# Pg8_JTAG_Interface_LEDs_Decoupling_Capac.net
KiCad netlist of a schematic drawn in Altium Designer
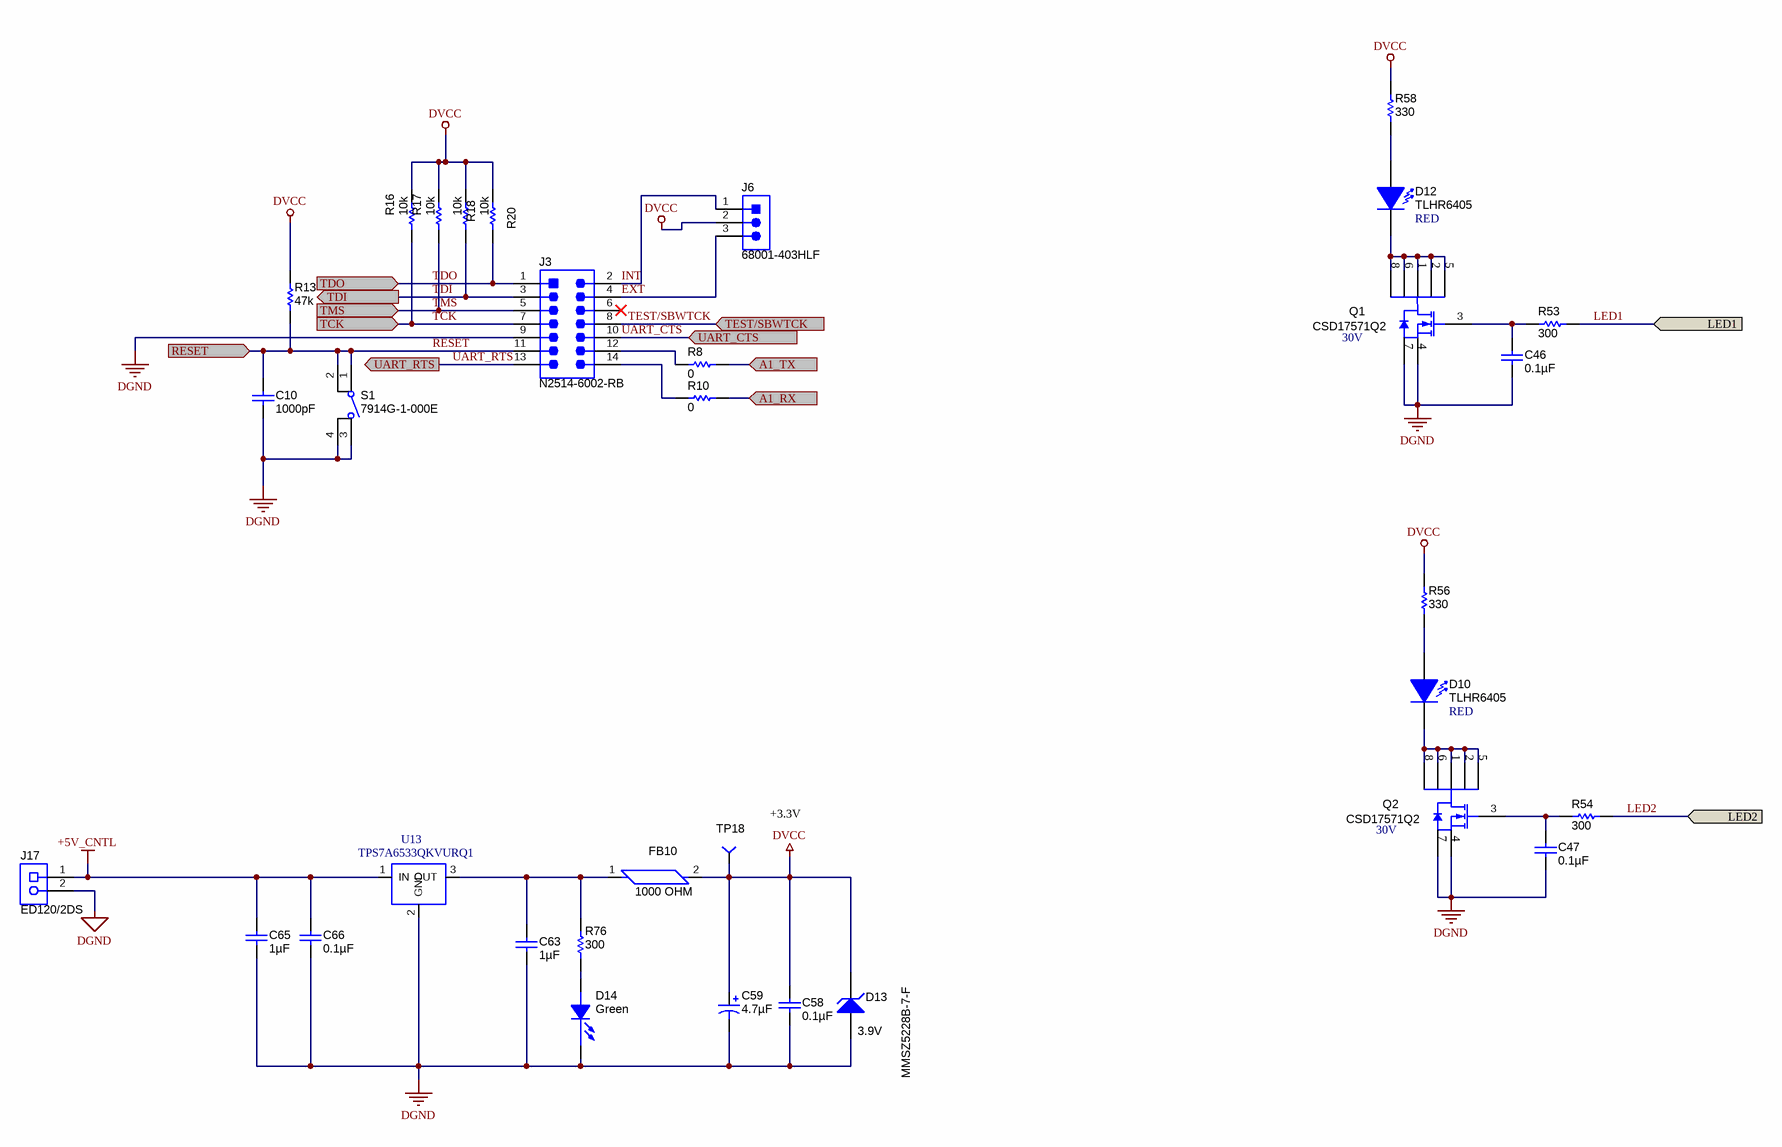
[diagram p0: Pg8.JTAG Interface + LEDs + Decoupling Capacitors.SchDoc]

(export (version "E")
  (design (tool "Eeschema 10.0.6"))
  (components
    (comp (ref "C10")
      (value "06035A102KAT2A")
      (footprint "0603")
      (description "CAP, CERM, 1000 pF, 50 V, +/- 10%, C0G/NP0, 0603")
      (fields
        (field (name "VALUEDISPLAYED") "1000pF")
        (field (name "MANUFACTURER") "AVX")
        (field (name "PUBLISHER") "Texas Instruments")
      )
      (libsource (lib "Capacitor_Ceramic") (part "06035A102KAT2A"))
    )
    (comp (ref "C46")
      (value "06033C104JAT2A")
      (footprint "0603")
      (description "CAP, CERM, 0.1uF, 25V, +/-5%, X7R, 0603")
      (fields
        (field (name "VALUEDISPLAYED") "0.1µF")
        (field (name "MANUFACTURER") "AVX")
        (field (name "PUBLISHER") "Texas Instruments")
      )
      (libsource (lib "Capacitor_Ceramic") (part "06033C104JAT2A"))
    )
    (comp (ref "C47")
      (value "06033C104JAT2A")
      (footprint "0603")
      (description "CAP, CERM, 0.1uF, 25V, +/-5%, X7R, 0603")
      (fields
        (field (name "VALUEDISPLAYED") "0.1µF")
        (field (name "MANUFACTURER") "AVX")
        (field (name "PUBLISHER") "Texas Instruments")
      )
      (libsource (lib "Capacitor_Ceramic") (part "06033C104JAT2A"))
    )
    (comp (ref "C58")
      (value "C0603C104K5RACTU")
      (footprint "0603")
      (description "CAP, CERM, 0.1uF, 50V, +/-10%, X7R, 0603")
      (fields
        (field (name "VALUEDISPLAYED") "0.1µF")
        (field (name "MANUFACTURER") "Kemet")
        (field (name "PUBLISHER") "Texas Instruments")
      )
      (libsource (lib "Capacitor_Ceramic") (part "C0603C104K5RACTU"))
    )
    (comp (ref "C59")
      (value "293D475X9035C2TE3")
      (footprint "6032-28")
      (description "CAP, TA, 4.7uF, 35V, +/-10%, 1.9 ohm, SMD")
      (fields
        (field (name "VALUEDISPLAYED") "4.7µF")
        (field (name "MANUFACTURER") "Vishay-Sprague")
        (field (name "PUBLISHER") "Texas Instruments")
      )
      (libsource (lib "Capacitor_Tantalum") (part "293D475X9035C2TE3"))
    )
    (comp (ref "C63")
      (value "GRM188R71C105KA12D")
      (footprint "0603")
      (description "CAP, CERM, 1 µF, 16 V, +/- 10%, X7R, 0603")
      (fields
        (field (name "VALUEDISPLAYED") "1µF")
        (field (name "MANUFACTURER") "MuRata")
        (field (name "PUBLISHER") "Texas Instruments")
      )
      (libsource (lib "Capacitor_Ceramic") (part "GRM188R71C105KA12D"))
    )
    (comp (ref "C65")
      (value "GRM188R71C105KA12D")
      (footprint "0603")
      (description "CAP, CERM, 1 µF, 16 V, +/- 10%, X7R, 0603")
      (fields
        (field (name "VALUEDISPLAYED") "1µF")
        (field (name "MANUFACTURER") "MuRata")
        (field (name "PUBLISHER") "Texas Instruments")
      )
      (libsource (lib "Capacitor_Ceramic") (part "GRM188R71C105KA12D"))
    )
    (comp (ref "C66")
      (value "C0603C104K5RACTU")
      (footprint "0603")
      (description "CAP, CERM, 0.1uF, 50V, +/-10%, X7R, 0603")
      (fields
        (field (name "VALUEDISPLAYED") "0.1µF")
        (field (name "MANUFACTURER") "Kemet")
        (field (name "PUBLISHER") "Texas Instruments")
      )
      (libsource (lib "Capacitor_Ceramic") (part "C0603C104K5RACTU"))
    )
    (comp (ref "D10")
      (value "TLHR6405")
      (footprint "LED_5MM")
      (description "LED, 5MM, RED, TH")
      (fields
        (field (name "MANUFACTURER") "VISHAY")
        (field (name "ALTIUM_VALUE") "RED")
        (field (name "SYMBOLCREATOR") "x0199378")
      )
      (libsource (lib "TLHR6405") (part "TLHR6405"))
    )
    (comp (ref "D12")
      (value "TLHR6405")
      (footprint "LED_5MM")
      (description "LED, 5MM, RED, TH")
      (fields
        (field (name "MANUFACTURER") "VISHAY")
        (field (name "ALTIUM_VALUE") "RED")
        (field (name "SYMBOLCREATOR") "x0199378")
      )
      (libsource (lib "TLHR6405") (part "TLHR6405"))
    )
    (comp (ref "D13")
      (value "MMSZ5228B-7-F")
      (footprint "sod-123")
      (description "DIODE ZENER 3.9V 500MW SOD123")
      (fields
        (field (name "ALTIUM_VALUE") "3.9V")
        (field (name "MANUFACTURER") "Diodes Incorporated")
        (field (name "PUBLISHER") "Texas Instruments")
      )
      (libsource (lib "ZenerDiodes") (part "1SMB5915BT3G"))
    )
    (comp (ref "D14")
      (value "Green")
      (footprint "LED0603AA")
      (description "LED SmartLED Green 570NM")
      (fields
        (field (name "PARTNUMBER") "LG L29K-G2J1-24-Z")
        (field (name "MANUFACTURER") "OSRAM")
        (field (name "PUBLISHER") "TI")
        (field (name "SYMBOLCREATOR") "x0120606")
      )
      (libsource (lib "TI-INDIA-ALTIUM") (part "LED_LG L29K-G2J1-24-Z"))
    )
    (comp (ref "FB10")
      (value "1000 OHM")
      (footprint "0603")
      (description "FERRITE CHIP 1000 OHM 300MA 0603")
      (fields
        (field (name "PARTNUMBER") "MMZ1608B102C")
        (field (name "MANUFACTURER") "TDK Corporation")
        (field (name "PUBLISHER") "TI")
      )
      (libsource (lib "TI-INDIA-ALTIUM") (part "MMZ1608B102C"))
    )
    (comp (ref "J3")
      (value "N2514-6002-RB")
      (footprint "3M_N2514-6002-RB")
      (description "Header, 7x2, 100mil, SMT")
      (fields
        (field (name "MANUFACTURER") "Molex")
        (field (name "SYMBOLCREATOR") "a0412235")
        (field (name "PUBLISHER") "Texas Instruments")
      )
      (libsource (lib "Connectors") (part "0015912140"))
    )
    (comp (ref "J6")
      (value "68001-403HLF")
      (footprint "HDR1X3")
      (description "3 pin berger")
      (fields
        (field (name "MANUFACTURER") "FCI")
        (field (name "SYMBOLCREATOR") "a0799628")
        (field (name "PUBLISHER") "Texas Instruments")
      )
      (libsource (lib "Connectors") (part "009155003301006"))
    )
    (comp (ref "J17")
      (value "ED120/2DS")
      (footprint "CONN_ED120-2DS")
      (description "TERMINAL BLOCK 5.08MM VERT 2POS, TH")
      (fields
        (field (name "MANUFACTURER") "On-Shore Technology")
        (field (name "SYMBOLCREATOR") "a0412235")
        (field (name "PUBLISHER") "Texas Instruments")
      )
      (libsource (lib "Connectors") (part "ED120/2DS"))
    )
    (comp (ref "Q1")
      (value "CSD17571Q2")
      (footprint "SON_CSD17571Q2")
      (description "MOSFET, N-CH, 30V, 22A, SON 2X2 MM")
      (fields
        (field (name "MANUFACTURER") "TEXAS INSTRUMENTS")
        (field (name "ALTIUM_VALUE") "30V")
        (field (name "SYMBOLCREATOR") "-")
      )
      (libsource (lib "CSD17571Q2") (part "CSD17571Q2"))
    )
    (comp (ref "Q2")
      (value "CSD17571Q2")
      (footprint "SON_CSD17571Q2")
      (description "MOSFET, N-CH, 30V, 22A, SON 2X2 MM")
      (fields
        (field (name "MANUFACTURER") "TEXAS INSTRUMENTS")
        (field (name "ALTIUM_VALUE") "30V")
        (field (name "SYMBOLCREATOR") "-")
      )
      (libsource (lib "CSD17571Q2") (part "CSD17571Q2"))
    )
    (comp (ref "R8")
      (value "0")
      (footprint "0603")
      (description "RES, 0 ohm, 5%, 0.1W, 0603")
      (fields
        (field (name "PARTNUMBER") "CRCW06030000Z0EA")
        (field (name "MANUFACTURER") "Vishay-Dale")
        (field (name "PUBLISHER") "Texas Instruments")
      )
      (libsource (lib "Resistor_0603") (part "CRCW06030000Z0EA"))
    )
    (comp (ref "R10")
      (value "0")
      (footprint "0603")
      (description "RES, 0 ohm, 5%, 0.1W, 0603")
      (fields
        (field (name "PARTNUMBER") "CRCW06030000Z0EA")
        (field (name "MANUFACTURER") "Vishay-Dale")
        (field (name "PUBLISHER") "Texas Instruments")
      )
      (libsource (lib "Resistor_0603") (part "CRCW06030000Z0EA"))
    )
    (comp (ref "R13")
      (value "47k")
      (footprint "0603")
      (description "RES, 47k ohm, 5%, 0.1W, 0603")
      (fields
        (field (name "PARTNUMBER") "CRCW060347K0JNEA")
        (field (name "MANUFACTURER") "Vishay-Dale")
        (field (name "PUBLISHER") "Texas Instruments")
      )
      (libsource (lib "Resistor_0603") (part "CRCW060347K0JNEA"))
    )
    (comp (ref "R16")
      (value "10k")
      (footprint "0603")
      (description "RES 10K OHM 1/10W 5% 0603 SMD")
      (fields
        (field (name "PARTNUMBER") "CRCW060310K0JNEA")
        (field (name "MANUFACTURER") "Vishay-Dale")
        (field (name "PUBLISHER") "Texas Instruments")
      )
      (libsource (lib "Resistor_0603") (part "RNCF0603TKY10K0"))
    )
    (comp (ref "R17")
      (value "10k")
      (footprint "0603")
      (description "RES 10K OHM 1/10W 5% 0603 SMD")
      (fields
        (field (name "PARTNUMBER") "CRCW060310K0JNEA")
        (field (name "MANUFACTURER") "Vishay-Dale")
        (field (name "PUBLISHER") "Texas Instruments")
      )
      (libsource (lib "Resistor_0603") (part "RNCF0603TKY10K0"))
    )
    (comp (ref "R18")
      (value "10k")
      (footprint "0603")
      (description "RES 10K OHM 1/10W 5% 0603 SMD")
      (fields
        (field (name "PARTNUMBER") "CRCW060310K0JNEA")
        (field (name "MANUFACTURER") "Vishay-Dale")
        (field (name "PUBLISHER") "Texas Instruments")
      )
      (libsource (lib "Resistor_0603") (part "RNCF0603TKY10K0"))
    )
    (comp (ref "R20")
      (value "10k")
      (footprint "0603")
      (description "RES 10K OHM 1/10W 5% 0603 SMD")
      (fields
        (field (name "PARTNUMBER") "CRCW060310K0JNEA")
        (field (name "MANUFACTURER") "Vishay-Dale")
        (field (name "PUBLISHER") "Texas Instruments")
      )
      (libsource (lib "Resistor_0603") (part "RNCF0603TKY10K0"))
    )
    (comp (ref "R53")
      (value "300")
      (footprint "0603")
      (description "RES, 300 ohm, 5%, 0.1W, 0603")
      (fields
        (field (name "PARTNUMBER") "CRCW0603300RJNEA")
        (field (name "MANUFACTURER") "Vishay-Dale")
        (field (name "PUBLISHER") "Texas Instruments")
      )
      (libsource (lib "Resistor_0603") (part "CRCW0603300RJNEA"))
    )
    (comp (ref "R54")
      (value "300")
      (footprint "0603")
      (description "RES, 300 ohm, 5%, 0.1W, 0603")
      (fields
        (field (name "PARTNUMBER") "CRCW0603300RJNEA")
        (field (name "MANUFACTURER") "Vishay-Dale")
        (field (name "PUBLISHER") "Texas Instruments")
      )
      (libsource (lib "Resistor_0603") (part "CRCW0603300RJNEA"))
    )
    (comp (ref "R56")
      (value "330")
      (footprint "0603")
      (description "RES, 330 ohm, 5%, 0.1W, 0603")
      (fields
        (field (name "PARTNUMBER") "CRCW0603330RJNEA")
        (field (name "MANUFACTURER") "Vishay-Dale")
        (field (name "PUBLISHER") "Texas Instruments")
      )
      (libsource (lib "Resistor_0603") (part "CRCW0603330RJNEA"))
    )
    (comp (ref "R58")
      (value "330")
      (footprint "0603")
      (description "RES, 330 ohm, 5%, 0.1W, 0603")
      (fields
        (field (name "PARTNUMBER") "CRCW0603330RJNEA")
        (field (name "MANUFACTURER") "Vishay-Dale")
        (field (name "PUBLISHER") "Texas Instruments")
      )
      (libsource (lib "Resistor_0603") (part "CRCW0603330RJNEA"))
    )
    (comp (ref "R76")
      (value "300")
      (footprint "0603")
      (description "RES, 300 ohm, 5%, 0.1W, 0603")
      (fields
        (field (name "PARTNUMBER") "CRCW0603300RJNEA")
        (field (name "MANUFACTURER") "Vishay-Dale")
        (field (name "PUBLISHER") "Texas Instruments")
      )
      (libsource (lib "Resistor_0603") (part "CRCW0603300RJNEA"))
    )
    (comp (ref "S1")
      (value "7914G-1-000E")
      (footprint "SW_7914G-1-000E")
      (description "Switch, Tactile, SPST-NO, 0.1A, 16V, SMT")
      (fields
        (field (name "MANUFACTURER") "Bourns")
        (field (name "SYMBOLCREATOR") "a0412235")
        (field (name "PUBLISHER") "Texas Instruments")
      )
      (libsource (lib "Switches") (part "7914G-1-000E"))
    )
    (comp (ref "TP18")
      (value "TP-040_RND")
      (footprint "TP-040_RND")
      (description "Test Point, O.040 Hole")
      (fields (field (name "MANUFACTURER") "STD"))
      (libsource (lib "PADSlegacy_Hardware") (part "TP-040_RND"))
    )
    (comp (ref "U13")
      (value "TPS7A6533QKVURQ1")
      (footprint "KVU_1")
      (description "IC, 300-mA 40-V LOW-DROPOUT REGULATOR WITH 25-uA QUIESCENT CURRENT")
      (fields (field (name "MANUFACTURER") "TI"))
      (libsource (lib "PADSlegacy_PMP") (part "TPS7A6533QKVURQ1"))
    )
  )
  (nets
    (net (code "1") (name "+5V_CNTL") (class "Default")
      (node (ref "C65") (pin "1") (pinfunction "1_1") (pintype "passive"))
      (node (ref "C66") (pin "1") (pinfunction "1_1") (pintype "passive"))
      (node (ref "J17") (pin "1") (pinfunction "1_1") (pintype "passive"))
      (node (ref "U13") (pin "1") (pinfunction "IN_1") (pintype "passive"))
    )
    (net (code "2") (name "/A1_RX") (class "Default")
      (node (ref "R10") (pin "2") (pinfunction "2_2") (pintype "passive"))
    )
    (net (code "3") (name "/A1_TX") (class "Default")
      (node (ref "R8") (pin "2") (pinfunction "2_2") (pintype "passive"))
    )
    (net (code "4") (name "/EXT") (class "Default")
      (node (ref "J3") (pin "4") (pinfunction "4_4") (pintype "passive"))
      (node (ref "J6") (pin "3") (pinfunction "3_3") (pintype "passive"))
    )
    (net (code "5") (name "/INT") (class "Default")
      (node (ref "J3") (pin "2") (pinfunction "2_2") (pintype "passive"))
      (node (ref "J6") (pin "1") (pinfunction "1_1") (pintype "passive"))
    )
    (net (code "6") (name "/LED1") (class "Default")
      (node (ref "R53") (pin "1") (pinfunction "1_1") (pintype "passive"))
    )
    (net (code "7") (name "/LED2") (class "Default")
      (node (ref "R54") (pin "1") (pinfunction "1_1") (pintype "passive"))
    )
    (net (code "8") (name "/RESET") (class "Default")
      (node (ref "C10") (pin "1") (pinfunction "1_1") (pintype "passive"))
      (node (ref "J3") (pin "11") (pinfunction "11_11") (pintype "passive"))
      (node (ref "R13") (pin "1") (pinfunction "1_1") (pintype "passive"))
      (node (ref "S1") (pin "1") (pinfunction "1_1") (pintype "passive"))
      (node (ref "S1") (pin "2") (pinfunction "2_2") (pintype "passive"))
    )
    (net (code "9") (name "/TCK") (class "Default")
      (node (ref "J3") (pin "7") (pinfunction "7_7") (pintype "passive"))
      (node (ref "R16") (pin "2") (pinfunction "2_2") (pintype "passive"))
    )
    (net (code "10") (name "/TDI") (class "Default")
      (node (ref "J3") (pin "3") (pinfunction "3_3") (pintype "passive"))
      (node (ref "R18") (pin "2") (pinfunction "2_2") (pintype "passive"))
    )
    (net (code "11") (name "/TDO") (class "Default")
      (node (ref "J3") (pin "1") (pinfunction "1_1") (pintype "passive"))
      (node (ref "R20") (pin "2") (pinfunction "2_2") (pintype "passive"))
    )
    (net (code "12") (name "/TEST{slash}SBWTCK") (class "Default")
      (node (ref "J3") (pin "8") (pinfunction "8_8") (pintype "passive"))
    )
    (net (code "13") (name "/TMS") (class "Default")
      (node (ref "J3") (pin "5") (pinfunction "5_5") (pintype "passive"))
      (node (ref "R17") (pin "2") (pinfunction "2_2") (pintype "passive"))
    )
    (net (code "14") (name "/UART_CTS") (class "Default")
      (node (ref "J3") (pin "10") (pinfunction "10_10") (pintype "passive"))
    )
    (net (code "15") (name "/UART_RTS") (class "Default")
      (node (ref "J3") (pin "13") (pinfunction "13_13") (pintype "passive"))
    )
    (net (code "16") (name "DGND") (class "Default")
      (node (ref "C10") (pin "2") (pinfunction "2_2") (pintype "passive"))
      (node (ref "C46") (pin "2") (pinfunction "2_2") (pintype "passive"))
      (node (ref "C47") (pin "2") (pinfunction "2_2") (pintype "passive"))
      (node (ref "C58") (pin "2") (pinfunction "2_2") (pintype "passive"))
      (node (ref "C59") (pin "2") (pinfunction "-_2") (pintype "passive"))
      (node (ref "C63") (pin "2") (pinfunction "2_2") (pintype "passive"))
      (node (ref "C65") (pin "2") (pinfunction "2_2") (pintype "passive"))
      (node (ref "C66") (pin "2") (pinfunction "2_2") (pintype "passive"))
      (node (ref "D13") (pin "2") (pinfunction "A_2") (pintype "passive"))
      (node (ref "D14") (pin "1") (pinfunction "C_1") (pintype "passive"))
      (node (ref "J17") (pin "2") (pinfunction "2_2") (pintype "passive"))
      (node (ref "J3") (pin "9") (pinfunction "9_9") (pintype "passive"))
      (node (ref "Q1") (pin "4") (pinfunction "S_4") (pintype "passive"))
      (node (ref "Q1") (pin "7") (pinfunction "S_7") (pintype "passive"))
      (node (ref "Q2") (pin "4") (pinfunction "S_4") (pintype "passive"))
      (node (ref "Q2") (pin "7") (pinfunction "S_7") (pintype "passive"))
      (node (ref "S1") (pin "3") (pinfunction "3_3") (pintype "passive"))
      (node (ref "S1") (pin "4") (pinfunction "4_4") (pintype "passive"))
      (node (ref "U13") (pin "2") (pinfunction "GND_2") (pintype "passive"))
    )
    (net (code "17") (name "DVCC") (class "Default")
      (node (ref "C58") (pin "1") (pinfunction "1_1") (pintype "passive"))
      (node (ref "C59") (pin "1") (pinfunction "+_1") (pintype "passive"))
      (node (ref "D13") (pin "1") (pinfunction "K_1") (pintype "passive"))
      (node (ref "FB10") (pin "2") (pinfunction "2_2") (pintype "passive"))
      (node (ref "J6") (pin "2") (pinfunction "2_2") (pintype "passive"))
      (node (ref "R13") (pin "2") (pinfunction "2_2") (pintype "passive"))
      (node (ref "R16") (pin "1") (pinfunction "1_1") (pintype "passive"))
      (node (ref "R17") (pin "1") (pinfunction "1_1") (pintype "passive"))
      (node (ref "R18") (pin "1") (pinfunction "1_1") (pintype "passive"))
      (node (ref "R20") (pin "1") (pinfunction "1_1") (pintype "passive"))
      (node (ref "R56") (pin "2") (pinfunction "2_2") (pintype "passive"))
      (node (ref "R58") (pin "2") (pinfunction "2_2") (pintype "passive"))
      (node (ref "TP18") (pin "1") (pinfunction "1_1") (pintype "passive"))
    )
    (net (code "18") (name "Net-(D10-A)") (class "Default")
      (node (ref "D10") (pin "2") (pinfunction "A_2") (pintype "passive"))
      (node (ref "R56") (pin "1") (pinfunction "1_1") (pintype "passive"))
    )
    (net (code "19") (name "Net-(D10-K)") (class "Default")
      (node (ref "D10") (pin "1") (pinfunction "K_1") (pintype "passive"))
      (node (ref "Q2") (pin "1") (pinfunction "D_1") (pintype "passive"))
      (node (ref "Q2") (pin "2") (pinfunction "D_2") (pintype "passive"))
      (node (ref "Q2") (pin "5") (pinfunction "D_5") (pintype "passive"))
      (node (ref "Q2") (pin "6") (pinfunction "D_6") (pintype "passive"))
      (node (ref "Q2") (pin "8") (pinfunction "D_8") (pintype "passive"))
    )
    (net (code "20") (name "Net-(D12-A)") (class "Default")
      (node (ref "D12") (pin "2") (pinfunction "A_2") (pintype "passive"))
      (node (ref "R58") (pin "1") (pinfunction "1_1") (pintype "passive"))
    )
    (net (code "21") (name "Net-(D12-K)") (class "Default")
      (node (ref "D12") (pin "1") (pinfunction "K_1") (pintype "passive"))
      (node (ref "Q1") (pin "1") (pinfunction "D_1") (pintype "passive"))
      (node (ref "Q1") (pin "2") (pinfunction "D_2") (pintype "passive"))
      (node (ref "Q1") (pin "5") (pinfunction "D_5") (pintype "passive"))
      (node (ref "Q1") (pin "6") (pinfunction "D_6") (pintype "passive"))
      (node (ref "Q1") (pin "8") (pinfunction "D_8") (pintype "passive"))
    )
    (net (code "22") (name "Net-(D14-A)") (class "Default")
      (node (ref "D14") (pin "2") (pinfunction "A_2") (pintype "passive"))
      (node (ref "R76") (pin "1") (pinfunction "1_1") (pintype "passive"))
    )
    (net (code "23") (name "Net-(J3-Pad12)") (class "Default")
      (node (ref "J3") (pin "12") (pinfunction "12_12") (pintype "passive"))
      (node (ref "R8") (pin "1") (pinfunction "1_1") (pintype "passive"))
    )
    (net (code "24") (name "Net-(J3-Pad14)") (class "Default")
      (node (ref "J3") (pin "14") (pinfunction "14_14") (pintype "passive"))
      (node (ref "R10") (pin "1") (pinfunction "1_1") (pintype "passive"))
    )
    (net (code "25") (name "Net-(Q1-G)") (class "Default")
      (node (ref "C46") (pin "1") (pinfunction "1_1") (pintype "passive"))
      (node (ref "Q1") (pin "3") (pinfunction "G_3") (pintype "passive"))
      (node (ref "R53") (pin "2") (pinfunction "2_2") (pintype "passive"))
    )
    (net (code "26") (name "Net-(Q2-G)") (class "Default")
      (node (ref "C47") (pin "1") (pinfunction "1_1") (pintype "passive"))
      (node (ref "Q2") (pin "3") (pinfunction "G_3") (pintype "passive"))
      (node (ref "R54") (pin "2") (pinfunction "2_2") (pintype "passive"))
    )
    (net (code "27") (name "Net-(U13-OUT)") (class "Default")
      (node (ref "C63") (pin "1") (pinfunction "1_1") (pintype "passive"))
      (node (ref "FB10") (pin "1") (pinfunction "1_1") (pintype "passive"))
      (node (ref "R76") (pin "2") (pinfunction "2_2") (pintype "passive"))
      (node (ref "U13") (pin "3") (pinfunction "OUT_3") (pintype "passive"))
    )
    (net (code "28") (name "unconnected-(J3-Pad6)") (class "Default")
      (node (ref "J3") (pin "6") (pinfunction "6_6") (pintype "passive+no_connect"))
    )
  )
)
